# esp7segcounter-v1.net
KiCad netlist of a schematic drawn in EAGLE
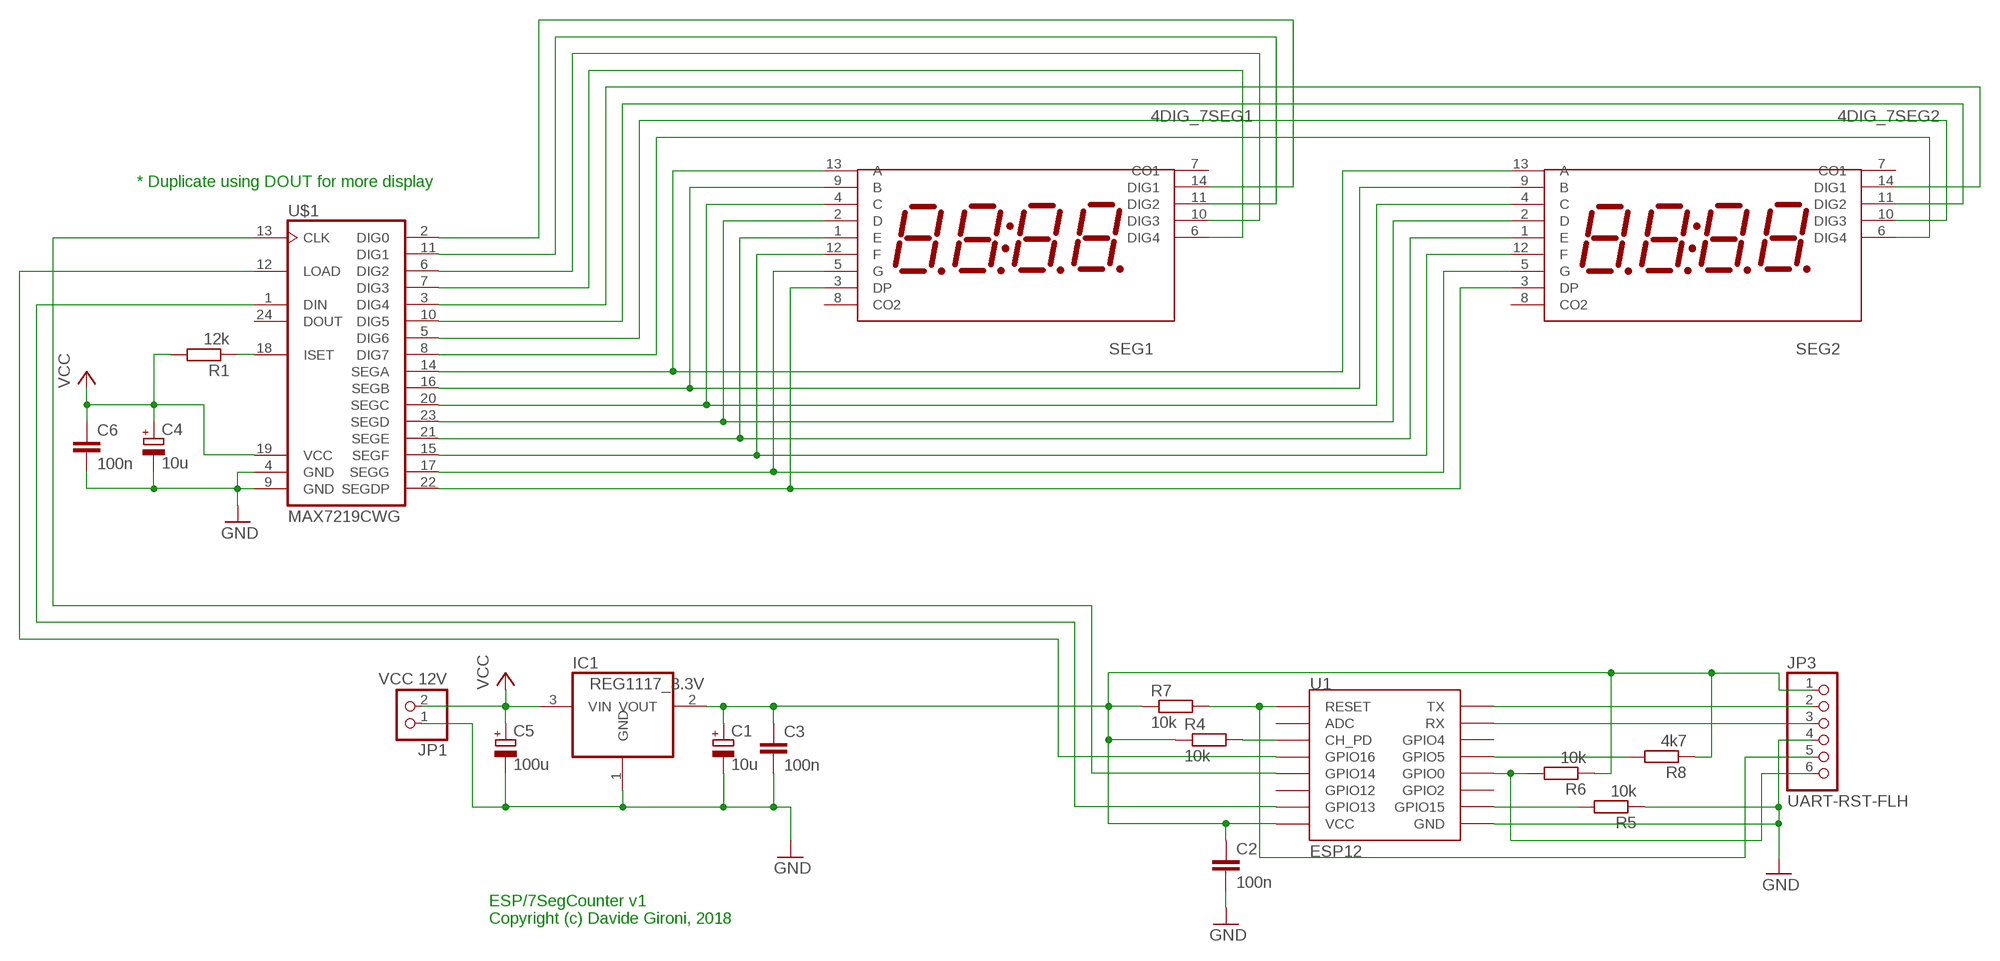
[diagram p0: schematic, sheet 1]

(export (version "E")
  (design (tool "Eeschema 10.0.6"))
  (components
    (comp (ref "4DIG_7SEG1")
      (value "SEG1")
      (footprint "eagle-import:4DIG_7SEG")
      (libsource (lib "eagle-import") (part "4DIG_7SEG"))
    )
    (comp (ref "4DIG_7SEG2")
      (value "SEG2")
      (footprint "eagle-import:4DIG_7SEG")
      (libsource (lib "eagle-import") (part "4DIG_7SEG"))
    )
    (comp (ref "C1")
      (value "10u")
      (footprint "eagle-import:B_3528-21R")
      (libsource (lib "eagle-import") (part "CPOL-EUB/3528-21R"))
    )
    (comp (ref "C2")
      (value "100n")
      (footprint "eagle-import:C0603")
      (libsource (lib "eagle-import") (part "C-EUC0603"))
    )
    (comp (ref "C3")
      (value "100n")
      (footprint "eagle-import:C0603")
      (libsource (lib "eagle-import") (part "C-EUC0603"))
    )
    (comp (ref "C4")
      (value "10u")
      (footprint "eagle-import:B_3528-21R")
      (libsource (lib "eagle-import") (part "CPOL-EUB/3528-21R"))
    )
    (comp (ref "C5")
      (value "100u")
      (footprint "eagle-import:E3,5-8")
      (libsource (lib "eagle-import") (part "CPOL-EUE3.5-8"))
    )
    (comp (ref "C6")
      (value "100n")
      (footprint "eagle-import:C0603")
      (libsource (lib "eagle-import") (part "C-EUC0603"))
    )
    (comp (ref "IC1")
      (value "REG1117_3.3V")
      (footprint "eagle-import:SOT223")
      (fields (field (name "MPN") "REG1117"))
      (libsource (lib "eagle-import") (part "REG1117"))
    )
    (comp (ref "JP1")
      (value "VCC 12V")
      (footprint "eagle-import:1X02")
      (libsource (lib "eagle-import") (part "PINHD-1X2"))
    )
    (comp (ref "JP3")
      (value "UART-RST-FLH")
      (footprint "eagle-import:1X06")
      (libsource (lib "eagle-import") (part "PINHD-1X6"))
    )
    (comp (ref "R1")
      (value "12k")
      (footprint "eagle-import:R0603")
      (libsource (lib "eagle-import") (part "R-EU_R0603"))
    )
    (comp (ref "R4")
      (value "10k")
      (footprint "eagle-import:R0603")
      (libsource (lib "eagle-import") (part "R-EU_R0603"))
    )
    (comp (ref "R5")
      (value "10k")
      (footprint "eagle-import:R0603")
      (libsource (lib "eagle-import") (part "R-EU_R0603"))
    )
    (comp (ref "R6")
      (value "10k")
      (footprint "eagle-import:R0603")
      (libsource (lib "eagle-import") (part "R-EU_R0603"))
    )
    (comp (ref "R7")
      (value "10k")
      (footprint "eagle-import:R0603")
      (libsource (lib "eagle-import") (part "R-EU_R0603"))
    )
    (comp (ref "R8")
      (value "4k7")
      (footprint "eagle-import:R0603")
      (libsource (lib "eagle-import") (part "R-EU_R0603"))
    )
    (comp (ref "U$1")
      (value "MAX7219CWG")
      (footprint "eagle-import:SO24L")
      (libsource (lib "eagle-import") (part "MAX7219CWG"))
    )
    (comp (ref "U1")
      (value "ESP12")
      (footprint "eagle-import:ESP12-SMD")
      (libsource (lib "eagle-import") (part "ESP12SMD"))
    )
  )
  (nets
    (net (code "1") (name "GND") (class "Default")
      (node (ref "C1") (pin "-") (pinfunction "-_-") (pintype "passive"))
      (node (ref "C2") (pin "2") (pinfunction "2_2") (pintype "passive"))
      (node (ref "C3") (pin "2") (pinfunction "2_2") (pintype "passive"))
      (node (ref "C4") (pin "-") (pinfunction "-_-") (pintype "passive"))
      (node (ref "C5") (pin "-") (pinfunction "-_-") (pintype "passive"))
      (node (ref "C6") (pin "2") (pinfunction "2_2") (pintype "passive"))
      (node (ref "IC1") (pin "1") (pinfunction "GND_1") (pintype "power_in"))
      (node (ref "JP1") (pin "1") (pinfunction "1_1") (pintype "passive"))
      (node (ref "JP3") (pin "4") (pinfunction "4_4") (pintype "passive"))
      (node (ref "R5") (pin "1") (pinfunction "1_1") (pintype "passive"))
      (node (ref "U$1") (pin "4") (pinfunction "GND_4") (pintype "power_in"))
      (node (ref "U$1") (pin "9") (pinfunction "GND_9") (pintype "power_in"))
      (node (ref "U1") (pin "GND") (pinfunction "GND_GND") (pintype "bidirectional"))
    )
    (net (code "2") (name "Net-(4DIG_7SEG1-A)") (class "Default")
      (node (ref "4DIG_7SEG1") (pin "13") (pinfunction "A_13") (pintype "bidirectional"))
      (node (ref "4DIG_7SEG2") (pin "13") (pinfunction "A_13") (pintype "bidirectional"))
      (node (ref "U$1") (pin "14") (pinfunction "SEGA_14") (pintype "output"))
    )
    (net (code "3") (name "Net-(4DIG_7SEG1-B)") (class "Default")
      (node (ref "4DIG_7SEG1") (pin "9") (pinfunction "B_9") (pintype "bidirectional"))
      (node (ref "4DIG_7SEG2") (pin "9") (pinfunction "B_9") (pintype "bidirectional"))
      (node (ref "U$1") (pin "16") (pinfunction "SEGB_16") (pintype "output"))
    )
    (net (code "4") (name "Net-(4DIG_7SEG1-C)") (class "Default")
      (node (ref "4DIG_7SEG1") (pin "4") (pinfunction "C_4") (pintype "bidirectional"))
      (node (ref "4DIG_7SEG2") (pin "4") (pinfunction "C_4") (pintype "bidirectional"))
      (node (ref "U$1") (pin "20") (pinfunction "SEGC_20") (pintype "output"))
    )
    (net (code "5") (name "Net-(4DIG_7SEG1-D)") (class "Default")
      (node (ref "4DIG_7SEG1") (pin "2") (pinfunction "D_2") (pintype "bidirectional"))
      (node (ref "4DIG_7SEG2") (pin "2") (pinfunction "D_2") (pintype "bidirectional"))
      (node (ref "U$1") (pin "23") (pinfunction "SEGD_23") (pintype "output"))
    )
    (net (code "6") (name "Net-(4DIG_7SEG1-DIG1)") (class "Default")
      (node (ref "4DIG_7SEG1") (pin "14") (pinfunction "DIG1_14") (pintype "bidirectional"))
      (node (ref "U$1") (pin "2") (pinfunction "DIG0_2") (pintype "output"))
    )
    (net (code "7") (name "Net-(4DIG_7SEG1-DIG2)") (class "Default")
      (node (ref "4DIG_7SEG1") (pin "11") (pinfunction "DIG2_11") (pintype "bidirectional"))
      (node (ref "U$1") (pin "11") (pinfunction "DIG1_11") (pintype "output"))
    )
    (net (code "8") (name "Net-(4DIG_7SEG1-DIG3)") (class "Default")
      (node (ref "4DIG_7SEG1") (pin "10") (pinfunction "DIG3_10") (pintype "bidirectional"))
      (node (ref "U$1") (pin "6") (pinfunction "DIG2_6") (pintype "output"))
    )
    (net (code "9") (name "Net-(4DIG_7SEG1-DIG4)") (class "Default")
      (node (ref "4DIG_7SEG1") (pin "6") (pinfunction "DIG4_6") (pintype "bidirectional"))
      (node (ref "U$1") (pin "7") (pinfunction "DIG3_7") (pintype "output"))
    )
    (net (code "10") (name "Net-(4DIG_7SEG1-DP)") (class "Default")
      (node (ref "4DIG_7SEG1") (pin "3") (pinfunction "DP_3") (pintype "bidirectional"))
      (node (ref "4DIG_7SEG2") (pin "3") (pinfunction "DP_3") (pintype "bidirectional"))
      (node (ref "U$1") (pin "22") (pinfunction "SEGDP_22") (pintype "output"))
    )
    (net (code "11") (name "Net-(4DIG_7SEG1-E)") (class "Default")
      (node (ref "4DIG_7SEG1") (pin "1") (pinfunction "E_1") (pintype "bidirectional"))
      (node (ref "4DIG_7SEG2") (pin "1") (pinfunction "E_1") (pintype "bidirectional"))
      (node (ref "U$1") (pin "21") (pinfunction "SEGE_21") (pintype "output"))
    )
    (net (code "12") (name "Net-(4DIG_7SEG1-F)") (class "Default")
      (node (ref "4DIG_7SEG1") (pin "12") (pinfunction "F_12") (pintype "bidirectional"))
      (node (ref "4DIG_7SEG2") (pin "12") (pinfunction "F_12") (pintype "bidirectional"))
      (node (ref "U$1") (pin "15") (pinfunction "SEGF_15") (pintype "output"))
    )
    (net (code "13") (name "Net-(4DIG_7SEG1-G)") (class "Default")
      (node (ref "4DIG_7SEG1") (pin "5") (pinfunction "G_5") (pintype "bidirectional"))
      (node (ref "4DIG_7SEG2") (pin "5") (pinfunction "G_5") (pintype "bidirectional"))
      (node (ref "U$1") (pin "17") (pinfunction "SEGG_17") (pintype "output"))
    )
    (net (code "14") (name "Net-(4DIG_7SEG2-DIG1)") (class "Default")
      (node (ref "4DIG_7SEG2") (pin "14") (pinfunction "DIG1_14") (pintype "bidirectional"))
      (node (ref "U$1") (pin "3") (pinfunction "DIG4_3") (pintype "output"))
    )
    (net (code "15") (name "Net-(4DIG_7SEG2-DIG2)") (class "Default")
      (node (ref "4DIG_7SEG2") (pin "11") (pinfunction "DIG2_11") (pintype "bidirectional"))
      (node (ref "U$1") (pin "10") (pinfunction "DIG5_10") (pintype "output"))
    )
    (net (code "16") (name "Net-(4DIG_7SEG2-DIG3)") (class "Default")
      (node (ref "4DIG_7SEG2") (pin "10") (pinfunction "DIG3_10") (pintype "bidirectional"))
      (node (ref "U$1") (pin "5") (pinfunction "DIG6_5") (pintype "output"))
    )
    (net (code "17") (name "Net-(4DIG_7SEG2-DIG4)") (class "Default")
      (node (ref "4DIG_7SEG2") (pin "6") (pinfunction "DIG4_6") (pintype "bidirectional"))
      (node (ref "U$1") (pin "8") (pinfunction "DIG7_8") (pintype "output"))
    )
    (net (code "18") (name "Net-(IC1-VOUT)") (class "Default")
      (node (ref "C1") (pin "+") (pinfunction "+_+") (pintype "passive"))
      (node (ref "C2") (pin "1") (pinfunction "1_1") (pintype "passive"))
      (node (ref "C3") (pin "1") (pinfunction "1_1") (pintype "passive"))
      (node (ref "IC1") (pin "2") (pinfunction "VOUT_2") (pintype "output"))
      (node (ref "JP3") (pin "1") (pinfunction "1_1") (pintype "passive"))
      (node (ref "R4") (pin "1") (pinfunction "1_1") (pintype "passive"))
      (node (ref "R6") (pin "1") (pinfunction "1_1") (pintype "passive"))
      (node (ref "R7") (pin "1") (pinfunction "1_1") (pintype "passive"))
      (node (ref "R8") (pin "1") (pinfunction "1_1") (pintype "passive"))
      (node (ref "U1") (pin "VCC") (pinfunction "VCC_VCC") (pintype "bidirectional"))
    )
    (net (code "19") (name "Net-(JP3-Pad5)") (class "Default")
      (node (ref "JP3") (pin "5") (pinfunction "5_5") (pintype "passive"))
      (node (ref "R7") (pin "2") (pinfunction "2_2") (pintype "passive"))
      (node (ref "U1") (pin "RESET") (pinfunction "RESET_RESET") (pintype "bidirectional"))
    )
    (net (code "20") (name "Net-(JP3-Pad6)") (class "Default")
      (node (ref "JP3") (pin "6") (pinfunction "6_6") (pintype "passive"))
      (node (ref "R6") (pin "2") (pinfunction "2_2") (pintype "passive"))
      (node (ref "U1") (pin "GPIO0") (pinfunction "GPIO0_GPIO0") (pintype "bidirectional"))
    )
    (net (code "21") (name "Net-(R4-Pad2)") (class "Default")
      (node (ref "R4") (pin "2") (pinfunction "2_2") (pintype "passive"))
      (node (ref "U1") (pin "CH_PD") (pinfunction "CH_PD_CH_PD") (pintype "bidirectional"))
    )
    (net (code "22") (name "Net-(R5-Pad2)") (class "Default")
      (node (ref "R5") (pin "2") (pinfunction "2_2") (pintype "passive"))
      (node (ref "U1") (pin "GPIO15") (pinfunction "GPIO15_GPIO15") (pintype "bidirectional"))
    )
    (net (code "23") (name "Net-(R8-Pad2)") (class "Default")
      (node (ref "R8") (pin "2") (pinfunction "2_2") (pintype "passive"))
      (node (ref "U1") (pin "GPIO5") (pinfunction "GPIO5_GPIO5") (pintype "bidirectional"))
    )
    (net (code "24") (name "Net-(U$1-CLK)") (class "Default")
      (node (ref "U$1") (pin "13") (pinfunction "CLK_13") (pintype "input"))
      (node (ref "U1") (pin "GPIO14") (pinfunction "GPIO14_GPIO14") (pintype "bidirectional"))
    )
    (net (code "25") (name "Net-(U$1-DIN)") (class "Default")
      (node (ref "U$1") (pin "1") (pinfunction "DIN_1") (pintype "input"))
      (node (ref "U1") (pin "GPIO13") (pinfunction "GPIO13_GPIO13") (pintype "bidirectional"))
    )
    (net (code "26") (name "Net-(U$1-ISET)") (class "Default")
      (node (ref "R1") (pin "1") (pinfunction "1_1") (pintype "passive"))
      (node (ref "U$1") (pin "18") (pinfunction "ISET_18") (pintype "input"))
    )
    (net (code "27") (name "Net-(U$1-LOAD)") (class "Default")
      (node (ref "U$1") (pin "12") (pinfunction "LOAD_12") (pintype "input"))
      (node (ref "U1") (pin "GPIO16") (pinfunction "GPIO16_GPIO16") (pintype "bidirectional"))
    )
    (net (code "28") (name "Net-(U1-RX)") (class "Default")
      (node (ref "JP3") (pin "3") (pinfunction "3_3") (pintype "passive"))
      (node (ref "U1") (pin "RXD0") (pinfunction "RX_RXD0") (pintype "bidirectional"))
    )
    (net (code "29") (name "Net-(U1-TX)") (class "Default")
      (node (ref "JP3") (pin "2") (pinfunction "2_2") (pintype "passive"))
      (node (ref "U1") (pin "TXD0") (pinfunction "TX_TXD0") (pintype "bidirectional"))
    )
    (net (code "30") (name "VCC") (class "Default")
      (node (ref "C4") (pin "+") (pinfunction "+_+") (pintype "passive"))
      (node (ref "C5") (pin "+") (pinfunction "+_+") (pintype "passive"))
      (node (ref "C6") (pin "1") (pinfunction "1_1") (pintype "passive"))
      (node (ref "IC1") (pin "3") (pinfunction "VIN_3") (pintype "input"))
      (node (ref "JP1") (pin "2") (pinfunction "2_2") (pintype "passive"))
      (node (ref "R1") (pin "2") (pinfunction "2_2") (pintype "passive"))
      (node (ref "U$1") (pin "19") (pinfunction "VCC_19") (pintype "power_in"))
    )
    (net (code "31") (name "unconnected-(4DIG_7SEG1-CO1-Pad7)") (class "Default")
      (node (ref "4DIG_7SEG1") (pin "7") (pinfunction "CO1_7") (pintype "bidirectional"))
    )
    (net (code "32") (name "unconnected-(4DIG_7SEG1-CO2-Pad8)") (class "Default")
      (node (ref "4DIG_7SEG1") (pin "8") (pinfunction "CO2_8") (pintype "bidirectional"))
    )
    (net (code "33") (name "unconnected-(4DIG_7SEG2-CO1-Pad7)") (class "Default")
      (node (ref "4DIG_7SEG2") (pin "7") (pinfunction "CO1_7") (pintype "bidirectional"))
    )
    (net (code "34") (name "unconnected-(4DIG_7SEG2-CO2-Pad8)") (class "Default")
      (node (ref "4DIG_7SEG2") (pin "8") (pinfunction "CO2_8") (pintype "bidirectional"))
    )
    (net (code "35") (name "unconnected-(U$1-DOUT-Pad24)") (class "Default")
      (node (ref "U$1") (pin "24") (pinfunction "DOUT_24") (pintype "output"))
    )
    (net (code "36") (name "unconnected-(U1-PadADC)") (class "Default")
      (node (ref "U1") (pin "ADC") (pinfunction "ADC_ADC") (pintype "bidirectional"))
    )
    (net (code "37") (name "unconnected-(U1-PadGPIO2)") (class "Default")
      (node (ref "U1") (pin "GPIO2") (pinfunction "GPIO2_GPIO2") (pintype "bidirectional"))
    )
    (net (code "38") (name "unconnected-(U1-PadGPIO4)") (class "Default")
      (node (ref "U1") (pin "GPIO4") (pinfunction "GPIO4_GPIO4") (pintype "bidirectional"))
    )
    (net (code "39") (name "unconnected-(U1-PadGPIO12)") (class "Default")
      (node (ref "U1") (pin "GPIO12") (pinfunction "GPIO12_GPIO12") (pintype "bidirectional"))
    )
  )
)
